# FPGA_Power.net
KiCad netlist of a schematic drawn in Altium Designer
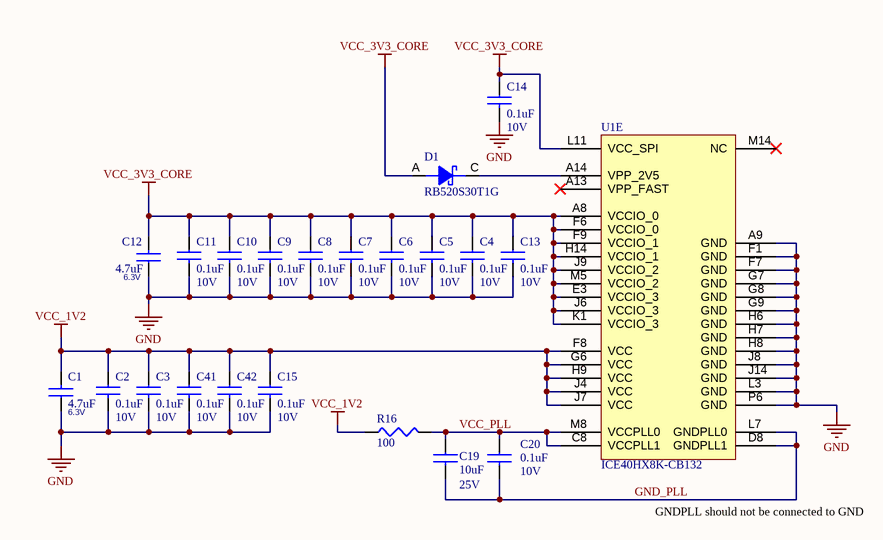
[diagram p0: FPGA_Power.SchDoc]

(export (version "E")
  (design (tool "Eeschema 10.0.6"))
  (components
    (comp (ref "C1")
      (value "4.7uF")
      (footprint "0402-IPCsm_55")
      (description "CAP CER 4.7UF 6.3V 20% X5R 0402")
      (fields (field (name "VOLTAGE") "6.3V") (field (name "MFG") "MURATA") (field (name "TOLERANCE") "20%"))
      (libsource (lib "SynapseLibrary") (part "CAP"))
    )
    (comp (ref "C2")
      (value "0.1uF")
      (footprint "0201-IPCsm_33")
      (description "CAP CER 0.1UF 10V 10% X5R 0201")
      (fields
        (field (name "VOLTAGE") "10V")
        (field (name "MFG") "Samsung Electro-Mechanics America, Inc")
        (field (name "TOLERANCE") "10%")
      )
      (libsource (lib "SynapseLibrary") (part "CAP"))
    )
    (comp (ref "C3")
      (value "0.1uF")
      (footprint "0201-IPCsm_33")
      (description "CAP CER 0.1UF 10V 10% X5R 0201")
      (fields
        (field (name "VOLTAGE") "10V")
        (field (name "MFG") "Samsung Electro-Mechanics America, Inc")
        (field (name "TOLERANCE") "10%")
      )
      (libsource (lib "SynapseLibrary") (part "CAP"))
    )
    (comp (ref "C4")
      (value "0.1uF")
      (footprint "0201-IPCsm_33")
      (description "CAP CER 0.1UF 10V 10% X5R 0201")
      (fields
        (field (name "VOLTAGE") "10V")
        (field (name "MFG") "Samsung Electro-Mechanics America, Inc")
        (field (name "TOLERANCE") "10%")
      )
      (libsource (lib "SynapseLibrary") (part "CAP"))
    )
    (comp (ref "C5")
      (value "0.1uF")
      (footprint "0201-IPCsm_33")
      (description "CAP CER 0.1UF 10V 10% X5R 0201")
      (fields
        (field (name "VOLTAGE") "10V")
        (field (name "MFG") "Samsung Electro-Mechanics America, Inc")
        (field (name "TOLERANCE") "10%")
      )
      (libsource (lib "SynapseLibrary") (part "CAP"))
    )
    (comp (ref "C6")
      (value "0.1uF")
      (footprint "0201-IPCsm_33")
      (description "CAP CER 0.1UF 10V 10% X5R 0201")
      (fields
        (field (name "VOLTAGE") "10V")
        (field (name "MFG") "Samsung Electro-Mechanics America, Inc")
        (field (name "TOLERANCE") "10%")
      )
      (libsource (lib "SynapseLibrary") (part "CAP"))
    )
    (comp (ref "C7")
      (value "0.1uF")
      (footprint "0201-IPCsm_33")
      (description "CAP CER 0.1UF 10V 10% X5R 0201")
      (fields
        (field (name "VOLTAGE") "10V")
        (field (name "MFG") "Samsung Electro-Mechanics America, Inc")
        (field (name "TOLERANCE") "10%")
      )
      (libsource (lib "SynapseLibrary") (part "CAP"))
    )
    (comp (ref "C8")
      (value "0.1uF")
      (footprint "0201-IPCsm_33")
      (description "CAP CER 0.1UF 10V 10% X5R 0201")
      (fields
        (field (name "VOLTAGE") "10V")
        (field (name "MFG") "Samsung Electro-Mechanics America, Inc")
        (field (name "TOLERANCE") "10%")
      )
      (libsource (lib "SynapseLibrary") (part "CAP"))
    )
    (comp (ref "C9")
      (value "0.1uF")
      (footprint "0201-IPCsm_33")
      (description "CAP CER 0.1UF 10V 10% X5R 0201")
      (fields
        (field (name "VOLTAGE") "10V")
        (field (name "MFG") "Samsung Electro-Mechanics America, Inc")
        (field (name "TOLERANCE") "10%")
      )
      (libsource (lib "SynapseLibrary") (part "CAP"))
    )
    (comp (ref "C10")
      (value "0.1uF")
      (footprint "0201-IPCsm_33")
      (description "CAP CER 0.1UF 10V 10% X5R 0201")
      (fields
        (field (name "VOLTAGE") "10V")
        (field (name "MFG") "Samsung Electro-Mechanics America, Inc")
        (field (name "TOLERANCE") "10%")
      )
      (libsource (lib "SynapseLibrary") (part "CAP"))
    )
    (comp (ref "C11")
      (value "0.1uF")
      (footprint "0201-IPCsm_33")
      (description "CAP CER 0.1UF 10V 10% X5R 0201")
      (fields
        (field (name "VOLTAGE") "10V")
        (field (name "MFG") "Samsung Electro-Mechanics America, Inc")
        (field (name "TOLERANCE") "10%")
      )
      (libsource (lib "SynapseLibrary") (part "CAP"))
    )
    (comp (ref "C12")
      (value "4.7uF")
      (footprint "0402-IPCsm_55")
      (description "CAP CER 4.7UF 6.3V 20% X5R 0402")
      (fields (field (name "VOLTAGE") "6.3V") (field (name "MFG") "MURATA") (field (name "TOLERANCE") "20%"))
      (libsource (lib "SynapseLibrary") (part "CAP"))
    )
    (comp (ref "C13")
      (value "0.1uF")
      (footprint "0201-IPCsm_33")
      (description "CAP CER 0.1UF 10V 10% X5R 0201")
      (fields
        (field (name "VOLTAGE") "10V")
        (field (name "MFG") "Samsung Electro-Mechanics America, Inc")
        (field (name "TOLERANCE") "10%")
      )
      (libsource (lib "SynapseLibrary") (part "CAP"))
    )
    (comp (ref "C14")
      (value "0.1uF")
      (footprint "0201-IPCsm_33")
      (description "CAP CER 0.1UF 10V 10% X5R 0201")
      (fields
        (field (name "VOLTAGE") "10V")
        (field (name "MFG") "Samsung Electro-Mechanics America, Inc")
        (field (name "TOLERANCE") "10%")
      )
      (libsource (lib "SynapseLibrary") (part "CAP"))
    )
    (comp (ref "C15")
      (value "0.1uF")
      (footprint "0201-IPCsm_33")
      (description "CAP CER 0.1UF 10V 10% X5R 0201")
      (fields
        (field (name "VOLTAGE") "10V")
        (field (name "MFG") "Samsung Electro-Mechanics America, Inc")
        (field (name "TOLERANCE") "10%")
      )
      (libsource (lib "SynapseLibrary") (part "CAP"))
    )
    (comp (ref "C19")
      (value "10uF")
      (footprint "0603-ipcsm_90")
      (description "CAP CER 10UF 25V 20% X5R 0603")
      (fields
        (field (name "VOLTAGE") "25V")
        (field (name "MFG") "Samsung Electro-Mechanics America, Inc")
        (field (name "TOLERANCE") "20%")
      )
      (libsource (lib "SynapseLibrary") (part "CAP"))
    )
    (comp (ref "C20")
      (value "0.1uF")
      (footprint "0201-IPCsm_33")
      (description "CAP CER 0.1UF 10V 10% X5R 0201")
      (fields
        (field (name "VOLTAGE") "10V")
        (field (name "MFG") "Samsung Electro-Mechanics America, Inc")
        (field (name "TOLERANCE") "10%")
      )
      (libsource (lib "SynapseLibrary") (part "CAP"))
    )
    (comp (ref "C41")
      (value "0.1uF")
      (footprint "0201-IPCsm_33")
      (description "CAP CER 0.1UF 10V 10% X5R 0201")
      (fields
        (field (name "VOLTAGE") "10V")
        (field (name "MFG") "Samsung Electro-Mechanics America, Inc")
        (field (name "TOLERANCE") "10%")
      )
      (libsource (lib "SynapseLibrary") (part "CAP"))
    )
    (comp (ref "C42")
      (value "0.1uF")
      (footprint "0201-IPCsm_33")
      (description "CAP CER 0.1UF 10V 10% X5R 0201")
      (fields
        (field (name "VOLTAGE") "10V")
        (field (name "MFG") "Samsung Electro-Mechanics America, Inc")
        (field (name "TOLERANCE") "10%")
      )
      (libsource (lib "SynapseLibrary") (part "CAP"))
    )
    (comp (ref "D1")
      (value "RB520S30T1G")
      (footprint "SOD523")
      (description "DIODE SCHOTTKY 30V 200MA SOD523")
      (fields (field (name "MFG") "On Semiconductor") (field (name "VOLTAGE") "30V"))
      (libsource (lib "SynapseLibrary") (part "DIODE_SCHOTTKY"))
    )
    (comp (ref "R16")
      (value "100")
      (footprint "0201-IPCsm_26")
      (description "RES 100 OHM 1/20W 1% 0201 SMD")
      (fields (field (name "TOLERANCE") "1.00%") (field (name "VOLTAGE") "50V"))
      (libsource (lib "SynapseLibrary") (part "RES"))
    )
    (comp (ref "U1")
      (value "ICE40HX8K-CB132")
      (footprint "LATC-csBGA-132")
      (description "IC FPGA 95 I/O 132CBGA")
      (fields (field (name "MFG") "Lattice Semiconductor Corporation") (field (name "VOLTAGE") "1.2-3.3v"))
      (libsource (lib "SynapseLibrary") (part "ICE40HX8K-CB132"))
    )
  )
  (nets
    (net (code "1") (name "/GND_PLL") (class "Default")
      (node (ref "C19") (pin "2") (pinfunction "2_2") (pintype "passive"))
      (node (ref "C20") (pin "2") (pinfunction "2_2") (pintype "passive"))
      (node (ref "U1") (pin "D8") (pinfunction "GNDPLL1_D8") (pintype "power_in"))
      (node (ref "U1") (pin "L7") (pinfunction "GNDPLL0_L7") (pintype "power_in"))
    )
    (net (code "2") (name "/VCC_PLL") (class "Default")
      (node (ref "C19") (pin "1") (pinfunction "1_1") (pintype "passive"))
      (node (ref "C20") (pin "1") (pinfunction "1_1") (pintype "passive"))
      (node (ref "R16") (pin "2") (pinfunction "2_2") (pintype "passive"))
      (node (ref "U1") (pin "C8") (pinfunction "VCCPLL1_C8") (pintype "power_in"))
      (node (ref "U1") (pin "M8") (pinfunction "VCCPLL0_M8") (pintype "power_in"))
    )
    (net (code "3") (name "GND") (class "Default")
      (node (ref "C1") (pin "1") (pinfunction "1_1") (pintype "passive"))
      (node (ref "C10") (pin "2") (pinfunction "2_2") (pintype "passive"))
      (node (ref "C11") (pin "2") (pinfunction "2_2") (pintype "passive"))
      (node (ref "C12") (pin "1") (pinfunction "1_1") (pintype "passive"))
      (node (ref "C13") (pin "2") (pinfunction "2_2") (pintype "passive"))
      (node (ref "C14") (pin "2") (pinfunction "2_2") (pintype "passive"))
      (node (ref "C15") (pin "2") (pinfunction "2_2") (pintype "passive"))
      (node (ref "C2") (pin "2") (pinfunction "2_2") (pintype "passive"))
      (node (ref "C3") (pin "2") (pinfunction "2_2") (pintype "passive"))
      (node (ref "C4") (pin "2") (pinfunction "2_2") (pintype "passive"))
      (node (ref "C41") (pin "2") (pinfunction "2_2") (pintype "passive"))
      (node (ref "C42") (pin "2") (pinfunction "2_2") (pintype "passive"))
      (node (ref "C5") (pin "2") (pinfunction "2_2") (pintype "passive"))
      (node (ref "C6") (pin "2") (pinfunction "2_2") (pintype "passive"))
      (node (ref "C7") (pin "2") (pinfunction "2_2") (pintype "passive"))
      (node (ref "C8") (pin "2") (pinfunction "2_2") (pintype "passive"))
      (node (ref "C9") (pin "2") (pinfunction "2_2") (pintype "passive"))
      (node (ref "U1") (pin "A9") (pinfunction "GND_A9") (pintype "power_in"))
      (node (ref "U1") (pin "F1") (pinfunction "GND_F1") (pintype "power_in"))
      (node (ref "U1") (pin "F7") (pinfunction "GND_F7") (pintype "power_in"))
      (node (ref "U1") (pin "G7") (pinfunction "GND_G7") (pintype "power_in"))
      (node (ref "U1") (pin "G8") (pinfunction "GND_G8") (pintype "power_in"))
      (node (ref "U1") (pin "G9") (pinfunction "GND_G9") (pintype "power_in"))
      (node (ref "U1") (pin "H6") (pinfunction "GND_H6") (pintype "power_in"))
      (node (ref "U1") (pin "H7") (pinfunction "GND_H7") (pintype "power_in"))
      (node (ref "U1") (pin "H8") (pinfunction "GND_H8") (pintype "power_in"))
      (node (ref "U1") (pin "J14") (pinfunction "GND_J14") (pintype "power_in"))
      (node (ref "U1") (pin "J8") (pinfunction "GND_J8") (pintype "power_in"))
      (node (ref "U1") (pin "L3") (pinfunction "GND_L3") (pintype "power_in"))
      (node (ref "U1") (pin "P6") (pinfunction "GND_P6") (pintype "power_in"))
    )
    (net (code "4") (name "Net-(U1E-VPP_2V5)") (class "Default")
      (node (ref "D1") (pin "C") (pinfunction "C_C") (pintype "passive"))
      (node (ref "U1") (pin "A14") (pinfunction "VPP_2V5_A14") (pintype "power_in"))
    )
    (net (code "5") (name "VCC_1V2") (class "Default")
      (node (ref "C1") (pin "2") (pinfunction "2_2") (pintype "passive"))
      (node (ref "C15") (pin "1") (pinfunction "1_1") (pintype "passive"))
      (node (ref "C2") (pin "1") (pinfunction "1_1") (pintype "passive"))
      (node (ref "C3") (pin "1") (pinfunction "1_1") (pintype "passive"))
      (node (ref "C41") (pin "1") (pinfunction "1_1") (pintype "passive"))
      (node (ref "C42") (pin "1") (pinfunction "1_1") (pintype "passive"))
      (node (ref "R16") (pin "1") (pinfunction "1_1") (pintype "passive"))
      (node (ref "U1") (pin "F8") (pinfunction "VCC_F8") (pintype "power_in"))
      (node (ref "U1") (pin "G6") (pinfunction "VCC_G6") (pintype "power_in"))
      (node (ref "U1") (pin "H9") (pinfunction "VCC_H9") (pintype "power_in"))
      (node (ref "U1") (pin "J4") (pinfunction "VCC_J4") (pintype "power_in"))
      (node (ref "U1") (pin "J7") (pinfunction "VCC_J7") (pintype "power_in"))
    )
    (net (code "6") (name "VCC_3V3_CORE") (class "Default")
      (node (ref "C10") (pin "1") (pinfunction "1_1") (pintype "passive"))
      (node (ref "C11") (pin "1") (pinfunction "1_1") (pintype "passive"))
      (node (ref "C12") (pin "2") (pinfunction "2_2") (pintype "passive"))
      (node (ref "C13") (pin "1") (pinfunction "1_1") (pintype "passive"))
      (node (ref "C14") (pin "1") (pinfunction "1_1") (pintype "passive"))
      (node (ref "C4") (pin "1") (pinfunction "1_1") (pintype "passive"))
      (node (ref "C5") (pin "1") (pinfunction "1_1") (pintype "passive"))
      (node (ref "C6") (pin "1") (pinfunction "1_1") (pintype "passive"))
      (node (ref "C7") (pin "1") (pinfunction "1_1") (pintype "passive"))
      (node (ref "C8") (pin "1") (pinfunction "1_1") (pintype "passive"))
      (node (ref "C9") (pin "1") (pinfunction "1_1") (pintype "passive"))
      (node (ref "D1") (pin "A") (pinfunction "A_A") (pintype "passive"))
      (node (ref "U1") (pin "A8") (pinfunction "VCCIO_0_A8") (pintype "power_in"))
      (node (ref "U1") (pin "E3") (pinfunction "VCCIO_3_E3") (pintype "power_in"))
      (node (ref "U1") (pin "F6") (pinfunction "VCCIO_0_F6") (pintype "power_in"))
      (node (ref "U1") (pin "F9") (pinfunction "VCCIO_1_F9") (pintype "power_in"))
      (node (ref "U1") (pin "H14") (pinfunction "VCCIO_1_H14") (pintype "power_in"))
      (node (ref "U1") (pin "J6") (pinfunction "VCCIO_3_J6") (pintype "power_in"))
      (node (ref "U1") (pin "J9") (pinfunction "VCCIO_2_J9") (pintype "power_in"))
      (node (ref "U1") (pin "K1") (pinfunction "VCCIO_3_K1") (pintype "power_in"))
      (node (ref "U1") (pin "L11") (pinfunction "VCC_SPI_L11") (pintype "power_in"))
      (node (ref "U1") (pin "M5") (pinfunction "VCCIO_2_M5") (pintype "power_in"))
    )
    (net (code "7") (name "unconnected-(U1E-NC-PadM14)") (class "Default")
      (node (ref "U1") (pin "M14") (pinfunction "NC_M14") (pintype "passive+no_connect"))
    )
    (net (code "8") (name "unconnected-(U1E-VPP_FAST-PadA13)") (class "Default")
      (node (ref "U1") (pin "A13") (pinfunction "VPP_FAST_A13") (pintype "power_in+no_connect"))
    )
  )
)
